# DeskLight.net
KiCad netlist of a schematic drawn in EAGLE
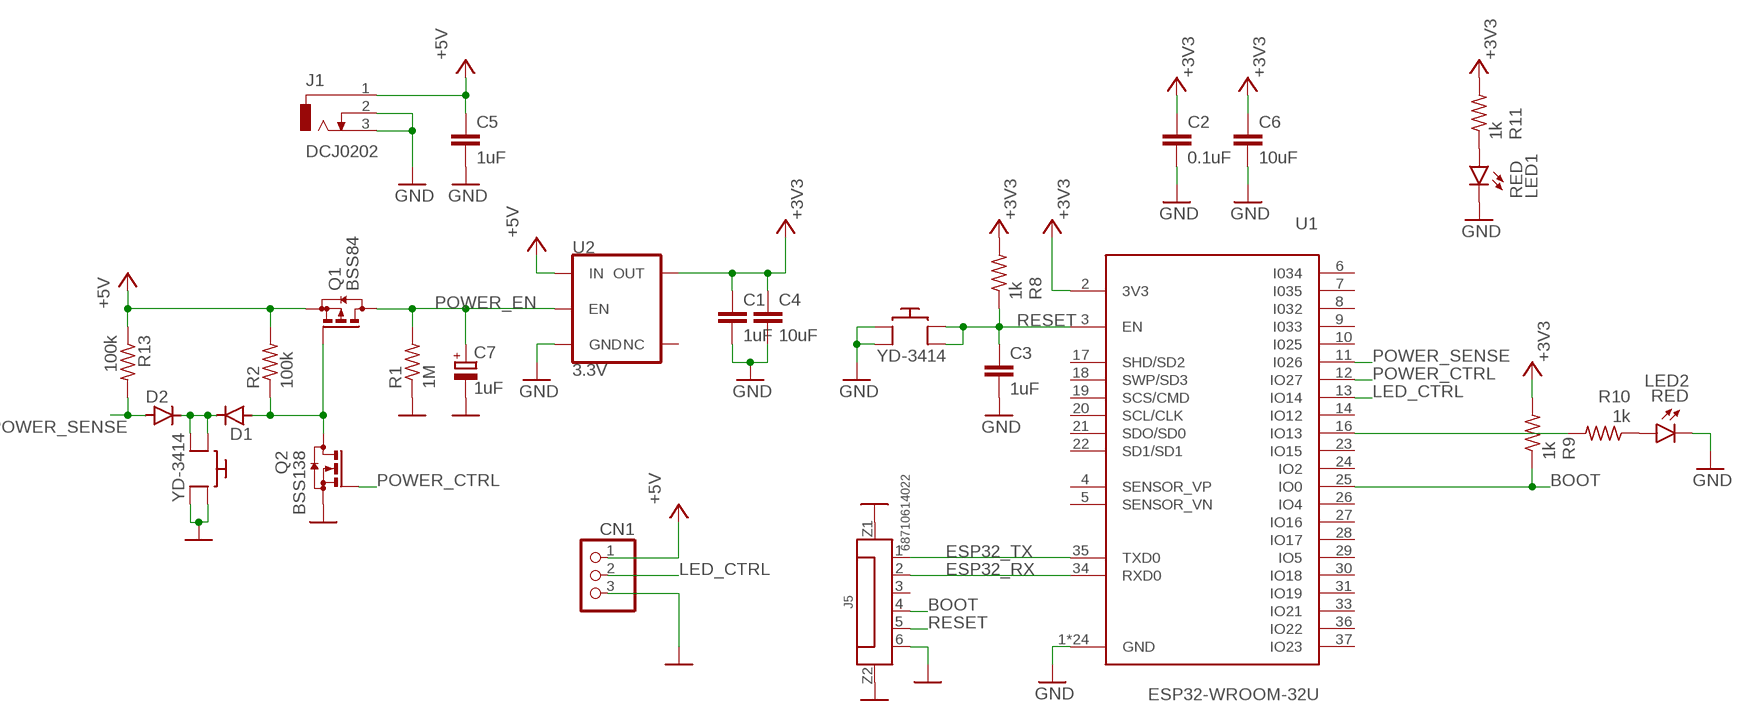
[diagram p0: schematic, sheet 1]

(export (version "E")
  (design (tool "Eeschema 10.0.6"))
  (components
    (comp (ref "C1")
      (value "1uF")
      (footprint "eagle-import:C0603")
      (libsource (lib "eagle-import") (part "C-EUC0603"))
    )
    (comp (ref "C2")
      (value "0.1uF")
      (footprint "eagle-import:C0603")
      (libsource (lib "eagle-import") (part "C-EUC0603"))
    )
    (comp (ref "C3")
      (value "1uF")
      (footprint "eagle-import:C0603")
      (libsource (lib "eagle-import") (part "C-EUC0603"))
    )
    (comp (ref "C4")
      (value "10uF")
      (footprint "eagle-import:C0805")
      (libsource (lib "eagle-import") (part "C-EUC0805"))
    )
    (comp (ref "C5")
      (value "1uF")
      (footprint "eagle-import:C0603")
      (libsource (lib "eagle-import") (part "C-EUC0603"))
    )
    (comp (ref "C6")
      (value "10uF")
      (footprint "eagle-import:C0805")
      (libsource (lib "eagle-import") (part "C-EUC0805"))
    )
    (comp (ref "C7")
      (value "1uF")
      (footprint "eagle-import:CT3216")
      (libsource (lib "eagle-import") (part "CPOL-EUCT3216"))
    )
    (comp (ref "CN1")
      (value "JST_3PIN")
      (footprint "eagle-import:JSTPH3")
      (libsource (lib "eagle-import") (part "JST_3PIN"))
    )
    (comp (ref "D1")
      (value "D-SOD123")
      (footprint "eagle-import:SOD123")
      (libsource (lib "eagle-import") (part "D-SOD123"))
    )
    (comp (ref "D2")
      (value "D-SOD123")
      (footprint "eagle-import:SOD123")
      (libsource (lib "eagle-import") (part "D-SOD123"))
    )
    (comp (ref "J1")
      (value "DCJ0202")
      (footprint "eagle-import:DCJ0202")
      (libsource (lib "eagle-import") (part "DCJ0202"))
    )
    (comp (ref "J5")
      (value "68710614022")
      (footprint "eagle-import:68710614022")
      (libsource (lib "eagle-import") (part "6871XX14022_68710614022"))
    )
    (comp (ref "LED1")
      (value "RED")
      (footprint "eagle-import:MICRO-SIDELED")
      (libsource (lib "eagle-import") (part "LEDMICRO-SIDELED"))
    )
    (comp (ref "LED2")
      (value "RED")
      (footprint "eagle-import:MICRO-SIDELED")
      (libsource (lib "eagle-import") (part "LEDMICRO-SIDELED"))
    )
    (comp (ref "Q1")
      (value "BSS84")
      (footprint "eagle-import:SOT23")
      (libsource (lib "eagle-import") (part "BSS84"))
    )
    (comp (ref "Q2")
      (value "BSS138")
      (footprint "eagle-import:SOT23")
      (libsource (lib "eagle-import") (part "BSS123"))
    )
    (comp (ref "R1")
      (value "1M")
      (footprint "eagle-import:R0603")
      (libsource (lib "eagle-import") (part "R-US_R0603"))
    )
    (comp (ref "R2")
      (value "100k")
      (footprint "eagle-import:R0603")
      (libsource (lib "eagle-import") (part "R-US_R0603"))
    )
    (comp (ref "R8")
      (value "1k")
      (footprint "eagle-import:R0603")
      (libsource (lib "eagle-import") (part "R-US_R0603"))
    )
    (comp (ref "R9")
      (value "1k")
      (footprint "eagle-import:R0603")
      (libsource (lib "eagle-import") (part "R-US_R0603"))
    )
    (comp (ref "R10")
      (value "1k")
      (footprint "eagle-import:R0603")
      (libsource (lib "eagle-import") (part "R-US_R0603"))
    )
    (comp (ref "R11")
      (value "1k")
      (footprint "eagle-import:R0603")
      (libsource (lib "eagle-import") (part "R-US_R0603"))
    )
    (comp (ref "R13")
      (value "100k")
      (footprint "eagle-import:R0603")
      (libsource (lib "eagle-import") (part "R-US_R0603"))
    )
    (comp (ref "U$1")
      (value "YD-3414")
      (footprint "eagle-import:YD-3414")
      (libsource (lib "eagle-import") (part "YD-3414"))
    )
    (comp (ref "U$67")
      (value "YD-3414")
      (footprint "eagle-import:YD-3414")
      (libsource (lib "eagle-import") (part "YD-3414"))
    )
    (comp (ref "U1")
      (value "ESP32-WROOM-32U")
      (footprint "eagle-import:XCVR_ESP32-WROOM-32U")
      (fields (field (name "MF") "Espressif Systems"))
      (libsource (lib "eagle-import") (part "ESP32-WROOM-32U"))
    )
    (comp (ref "U2")
      (value "3.3V")
      (footprint "eagle-import:SOT23-5")
      (libsource (lib "eagle-import") (part "V_REG_AP2112K-3.3V"))
    )
  )
  (nets
    (net (code "1") (name "+3V3") (class "Default")
      (node (ref "C1") (pin "1") (pinfunction "1_1") (pintype "passive"))
      (node (ref "C2") (pin "1") (pinfunction "1_1") (pintype "passive"))
      (node (ref "C4") (pin "1") (pinfunction "1_1") (pintype "passive"))
      (node (ref "C6") (pin "1") (pinfunction "1_1") (pintype "passive"))
      (node (ref "R11") (pin "2") (pinfunction "2_2") (pintype "passive"))
      (node (ref "R8") (pin "2") (pinfunction "2_2") (pintype "passive"))
      (node (ref "R9") (pin "2") (pinfunction "2_2") (pintype "passive"))
      (node (ref "U1") (pin "2") (pinfunction "3V3_2") (pintype "power_in"))
      (node (ref "U2") (pin "5") (pinfunction "OUT_5") (pintype "passive"))
    )
    (net (code "2") (name "+5V") (class "Default")
      (node (ref "C5") (pin "1") (pinfunction "1_1") (pintype "passive"))
      (node (ref "CN1") (pin "1") (pinfunction "1_1") (pintype "passive"))
      (node (ref "J1") (pin "1") (pinfunction "1_1") (pintype "passive"))
      (node (ref "Q1") (pin "2") (pinfunction "S_2") (pintype "passive"))
      (node (ref "R13") (pin "1") (pinfunction "1_1") (pintype "passive"))
      (node (ref "R2") (pin "2") (pinfunction "2_2") (pintype "passive"))
      (node (ref "U2") (pin "1") (pinfunction "IN_1") (pintype "input"))
    )
    (net (code "3") (name "/BOOT") (class "Default")
      (node (ref "J5") (pin "4") (pinfunction "4_4") (pintype "passive"))
      (node (ref "R9") (pin "1") (pinfunction "1_1") (pintype "passive"))
      (node (ref "U1") (pin "25") (pinfunction "IO0_25") (pintype "bidirectional"))
    )
    (net (code "4") (name "/ESP32_RX") (class "Default")
      (node (ref "J5") (pin "2") (pinfunction "2_2") (pintype "passive"))
      (node (ref "U1") (pin "34") (pinfunction "RXD0_34") (pintype "bidirectional"))
    )
    (net (code "5") (name "/ESP32_TX") (class "Default")
      (node (ref "J5") (pin "1") (pinfunction "1_1") (pintype "passive"))
      (node (ref "U1") (pin "35") (pinfunction "TXD0_35") (pintype "bidirectional"))
    )
    (net (code "6") (name "/LED_CTRL") (class "Default")
      (node (ref "CN1") (pin "2") (pinfunction "2_2") (pintype "passive"))
      (node (ref "U1") (pin "13") (pinfunction "IO14_13") (pintype "bidirectional"))
    )
    (net (code "7") (name "/POWER_CTRL") (class "Default")
      (node (ref "Q2") (pin "1") (pinfunction "G_1") (pintype "passive"))
      (node (ref "U1") (pin "12") (pinfunction "IO27_12") (pintype "bidirectional"))
    )
    (net (code "8") (name "/POWER_EN") (class "Default")
      (node (ref "C7") (pin "+") (pinfunction "+_+") (pintype "passive"))
      (node (ref "Q1") (pin "3") (pinfunction "D_3") (pintype "passive"))
      (node (ref "R1") (pin "2") (pinfunction "2_2") (pintype "passive"))
      (node (ref "U2") (pin "3") (pinfunction "EN_3") (pintype "input"))
    )
    (net (code "9") (name "/POWER_SENSE") (class "Default")
      (node (ref "D2") (pin "2") (pinfunction "A_2") (pintype "passive"))
      (node (ref "R13") (pin "2") (pinfunction "2_2") (pintype "passive"))
      (node (ref "U1") (pin "11") (pinfunction "I026_11") (pintype "bidirectional"))
    )
    (net (code "10") (name "/RESET") (class "Default")
      (node (ref "C3") (pin "1") (pinfunction "1_1") (pintype "passive"))
      (node (ref "J5") (pin "5") (pinfunction "5_5") (pintype "passive"))
      (node (ref "R8") (pin "1") (pinfunction "1_1") (pintype "passive"))
      (node (ref "U$1") (pin "P$1") (pinfunction "P$1_P$1") (pintype "bidirectional"))
      (node (ref "U$1") (pin "P$2") (pinfunction "P$2_P$2") (pintype "bidirectional"))
      (node (ref "U1") (pin "3") (pinfunction "EN_3") (pintype "input"))
    )
    (net (code "11") (name "GND") (class "Default")
      (node (ref "C1") (pin "2") (pinfunction "2_2") (pintype "passive"))
      (node (ref "C2") (pin "2") (pinfunction "2_2") (pintype "passive"))
      (node (ref "C3") (pin "2") (pinfunction "2_2") (pintype "passive"))
      (node (ref "C4") (pin "2") (pinfunction "2_2") (pintype "passive"))
      (node (ref "C5") (pin "2") (pinfunction "2_2") (pintype "passive"))
      (node (ref "C6") (pin "2") (pinfunction "2_2") (pintype "passive"))
      (node (ref "C7") (pin "-") (pinfunction "-_-") (pintype "passive"))
      (node (ref "CN1") (pin "3") (pinfunction "3_3") (pintype "passive"))
      (node (ref "J1") (pin "2") (pinfunction "2_2") (pintype "passive"))
      (node (ref "J1") (pin "3") (pinfunction "3_3") (pintype "passive"))
      (node (ref "J5") (pin "6") (pinfunction "6_6") (pintype "passive"))
      (node (ref "J5") (pin "Z1") (pinfunction "Z1_Z1") (pintype "passive"))
      (node (ref "J5") (pin "Z2") (pinfunction "Z2_Z2") (pintype "passive"))
      (node (ref "LED1") (pin "C") (pinfunction "C_C") (pintype "passive"))
      (node (ref "LED2") (pin "C") (pinfunction "C_C") (pintype "passive"))
      (node (ref "Q2") (pin "2") (pinfunction "S_2") (pintype "passive"))
      (node (ref "R1") (pin "1") (pinfunction "1_1") (pintype "passive"))
      (node (ref "U$1") (pin "P$3") (pinfunction "P$3_P$3") (pintype "bidirectional"))
      (node (ref "U$1") (pin "P$4") (pinfunction "P$4_P$4") (pintype "bidirectional"))
      (node (ref "U$67") (pin "P$3") (pinfunction "P$3_P$3") (pintype "bidirectional"))
      (node (ref "U$67") (pin "P$4") (pinfunction "P$4_P$4") (pintype "bidirectional"))
      (node (ref "U1") (pin "1") (pinfunction "GND_1") (pintype "power_in"))
      (node (ref "U1") (pin "15") (pinfunction "GND_15") (pintype "power_in"))
      (node (ref "U1") (pin "38") (pinfunction "GND_38") (pintype "power_in"))
      (node (ref "U1") (pin "G.1") (pinfunction "GND_G.1") (pintype "power_in"))
      (node (ref "U1") (pin "G.10") (pinfunction "GND_G.10") (pintype "power_in"))
      (node (ref "U1") (pin "G.11") (pinfunction "GND_G.11") (pintype "power_in"))
      (node (ref "U1") (pin "G.12") (pinfunction "GND_G.12") (pintype "power_in"))
      (node (ref "U1") (pin "G.13") (pinfunction "GND_G.13") (pintype "power_in"))
      (node (ref "U1") (pin "G.14") (pinfunction "GND_G.14") (pintype "power_in"))
      (node (ref "U1") (pin "G.15") (pinfunction "GND_G.15") (pintype "power_in"))
      (node (ref "U1") (pin "G.16") (pinfunction "GND_G.16") (pintype "power_in"))
      (node (ref "U1") (pin "G.17") (pinfunction "GND_G.17") (pintype "power_in"))
      (node (ref "U1") (pin "G.18") (pinfunction "GND_G.18") (pintype "power_in"))
      (node (ref "U1") (pin "G.19") (pinfunction "GND_G.19") (pintype "power_in"))
      (node (ref "U1") (pin "G.2") (pinfunction "GND_G.2") (pintype "power_in"))
      (node (ref "U1") (pin "G.20") (pinfunction "GND_G.20") (pintype "power_in"))
      (node (ref "U1") (pin "G.21") (pinfunction "GND_G.21") (pintype "power_in"))
      (node (ref "U1") (pin "G.22") (pinfunction "GND_G.22") (pintype "power_in"))
      (node (ref "U1") (pin "G.4") (pinfunction "GND_G.4") (pintype "power_in"))
      (node (ref "U1") (pin "G.5") (pinfunction "GND_G.5") (pintype "power_in"))
      (node (ref "U1") (pin "G.6") (pinfunction "GND_G.6") (pintype "power_in"))
      (node (ref "U1") (pin "G.7") (pinfunction "GND_G.7") (pintype "power_in"))
      (node (ref "U1") (pin "G.8") (pinfunction "GND_G.8") (pintype "power_in"))
      (node (ref "U1") (pin "G.9") (pinfunction "GND_G.9") (pintype "power_in"))
      (node (ref "U2") (pin "2") (pinfunction "GND_2") (pintype "input"))
    )
    (net (code "12") (name "Net-(D1-A)") (class "Default")
      (node (ref "D1") (pin "2") (pinfunction "A_2") (pintype "passive"))
      (node (ref "Q1") (pin "1") (pinfunction "G_1") (pintype "passive"))
      (node (ref "Q2") (pin "3") (pinfunction "D_3") (pintype "passive"))
      (node (ref "R2") (pin "1") (pinfunction "1_1") (pintype "passive"))
    )
    (net (code "13") (name "Net-(D1-C)") (class "Default")
      (node (ref "D1") (pin "1") (pinfunction "C_1") (pintype "passive"))
      (node (ref "D2") (pin "1") (pinfunction "C_1") (pintype "passive"))
      (node (ref "U$67") (pin "P$1") (pinfunction "P$1_P$1") (pintype "bidirectional"))
      (node (ref "U$67") (pin "P$2") (pinfunction "P$2_P$2") (pintype "bidirectional"))
    )
    (net (code "14") (name "Net-(LED1-PadA)") (class "Default")
      (node (ref "LED1") (pin "A") (pinfunction "A_A") (pintype "passive"))
      (node (ref "R11") (pin "1") (pinfunction "1_1") (pintype "passive"))
    )
    (net (code "15") (name "Net-(LED2-PadA)") (class "Default")
      (node (ref "LED2") (pin "A") (pinfunction "A_A") (pintype "passive"))
      (node (ref "R10") (pin "1") (pinfunction "1_1") (pintype "passive"))
    )
    (net (code "16") (name "Net-(U1-IO13)") (class "Default")
      (node (ref "R10") (pin "2") (pinfunction "2_2") (pintype "passive"))
      (node (ref "U1") (pin "16") (pinfunction "IO13_16") (pintype "bidirectional"))
    )
    (net (code "17") (name "unconnected-(J5-Pad3)") (class "Default")
      (node (ref "J5") (pin "3") (pinfunction "3_3") (pintype "passive"))
    )
    (net (code "18") (name "unconnected-(U1-I025-Pad10)") (class "Default")
      (node (ref "U1") (pin "10") (pinfunction "I025_10") (pintype "bidirectional"))
    )
    (net (code "19") (name "unconnected-(U1-I032-Pad8)") (class "Default")
      (node (ref "U1") (pin "8") (pinfunction "I032_8") (pintype "bidirectional"))
    )
    (net (code "20") (name "unconnected-(U1-I033-Pad9)") (class "Default")
      (node (ref "U1") (pin "9") (pinfunction "I033_9") (pintype "bidirectional"))
    )
    (net (code "21") (name "unconnected-(U1-I034-Pad6)") (class "Default")
      (node (ref "U1") (pin "6") (pinfunction "I034_6") (pintype "input"))
    )
    (net (code "22") (name "unconnected-(U1-I035-Pad7)") (class "Default")
      (node (ref "U1") (pin "7") (pinfunction "I035_7") (pintype "input"))
    )
    (net (code "23") (name "unconnected-(U1-IO2-Pad24)") (class "Default")
      (node (ref "U1") (pin "24") (pinfunction "IO2_24") (pintype "bidirectional"))
    )
    (net (code "24") (name "unconnected-(U1-IO4-Pad26)") (class "Default")
      (node (ref "U1") (pin "26") (pinfunction "IO4_26") (pintype "bidirectional"))
    )
    (net (code "25") (name "unconnected-(U1-IO5-Pad29)") (class "Default")
      (node (ref "U1") (pin "29") (pinfunction "IO5_29") (pintype "bidirectional"))
    )
    (net (code "26") (name "unconnected-(U1-IO12-Pad14)") (class "Default")
      (node (ref "U1") (pin "14") (pinfunction "IO12_14") (pintype "bidirectional"))
    )
    (net (code "27") (name "unconnected-(U1-IO15-Pad23)") (class "Default")
      (node (ref "U1") (pin "23") (pinfunction "IO15_23") (pintype "bidirectional"))
    )
    (net (code "28") (name "unconnected-(U1-IO16-Pad27)") (class "Default")
      (node (ref "U1") (pin "27") (pinfunction "IO16_27") (pintype "bidirectional"))
    )
    (net (code "29") (name "unconnected-(U1-IO17-Pad28)") (class "Default")
      (node (ref "U1") (pin "28") (pinfunction "IO17_28") (pintype "bidirectional"))
    )
    (net (code "30") (name "unconnected-(U1-IO18-Pad30)") (class "Default")
      (node (ref "U1") (pin "30") (pinfunction "IO18_30") (pintype "bidirectional"))
    )
    (net (code "31") (name "unconnected-(U1-IO19-Pad31)") (class "Default")
      (node (ref "U1") (pin "31") (pinfunction "IO19_31") (pintype "bidirectional"))
    )
    (net (code "32") (name "unconnected-(U1-IO21-Pad33)") (class "Default")
      (node (ref "U1") (pin "33") (pinfunction "IO21_33") (pintype "bidirectional"))
    )
    (net (code "33") (name "unconnected-(U1-IO22-Pad36)") (class "Default")
      (node (ref "U1") (pin "36") (pinfunction "IO22_36") (pintype "bidirectional"))
    )
    (net (code "34") (name "unconnected-(U1-IO23-Pad37)") (class "Default")
      (node (ref "U1") (pin "37") (pinfunction "IO23_37") (pintype "bidirectional"))
    )
    (net (code "35") (name "unconnected-(U1-SCL{slash}CLK-Pad20)") (class "Default")
      (node (ref "U1") (pin "20") (pinfunction "SCL/CLK_20") (pintype "bidirectional"))
    )
    (net (code "36") (name "unconnected-(U1-SCS{slash}CMD-Pad19)") (class "Default")
      (node (ref "U1") (pin "19") (pinfunction "SCS/CMD_19") (pintype "bidirectional"))
    )
    (net (code "37") (name "unconnected-(U1-SD1{slash}SD1-Pad22)") (class "Default")
      (node (ref "U1") (pin "22") (pinfunction "SD1/SD1_22") (pintype "bidirectional"))
    )
    (net (code "38") (name "unconnected-(U1-SDO{slash}SD0-Pad21)") (class "Default")
      (node (ref "U1") (pin "21") (pinfunction "SDO/SD0_21") (pintype "bidirectional"))
    )
    (net (code "39") (name "unconnected-(U1-SENSOR_VN-Pad5)") (class "Default")
      (node (ref "U1") (pin "5") (pinfunction "SENSOR_VN_5") (pintype "input"))
    )
    (net (code "40") (name "unconnected-(U1-SENSOR_VP-Pad4)") (class "Default")
      (node (ref "U1") (pin "4") (pinfunction "SENSOR_VP_4") (pintype "input"))
    )
    (net (code "41") (name "unconnected-(U1-SHD{slash}SD2-Pad17)") (class "Default")
      (node (ref "U1") (pin "17") (pinfunction "SHD/SD2_17") (pintype "bidirectional"))
    )
    (net (code "42") (name "unconnected-(U1-SWP{slash}SD3-Pad18)") (class "Default")
      (node (ref "U1") (pin "18") (pinfunction "SWP/SD3_18") (pintype "bidirectional"))
    )
    (net (code "43") (name "unconnected-(U2-NC-Pad4)") (class "Default")
      (node (ref "U2") (pin "4") (pinfunction "NC_4") (pintype "no_connect"))
    )
  )
)
